# TELM0002ADC.net
KiCad netlist of a schematic drawn in Altium Designer
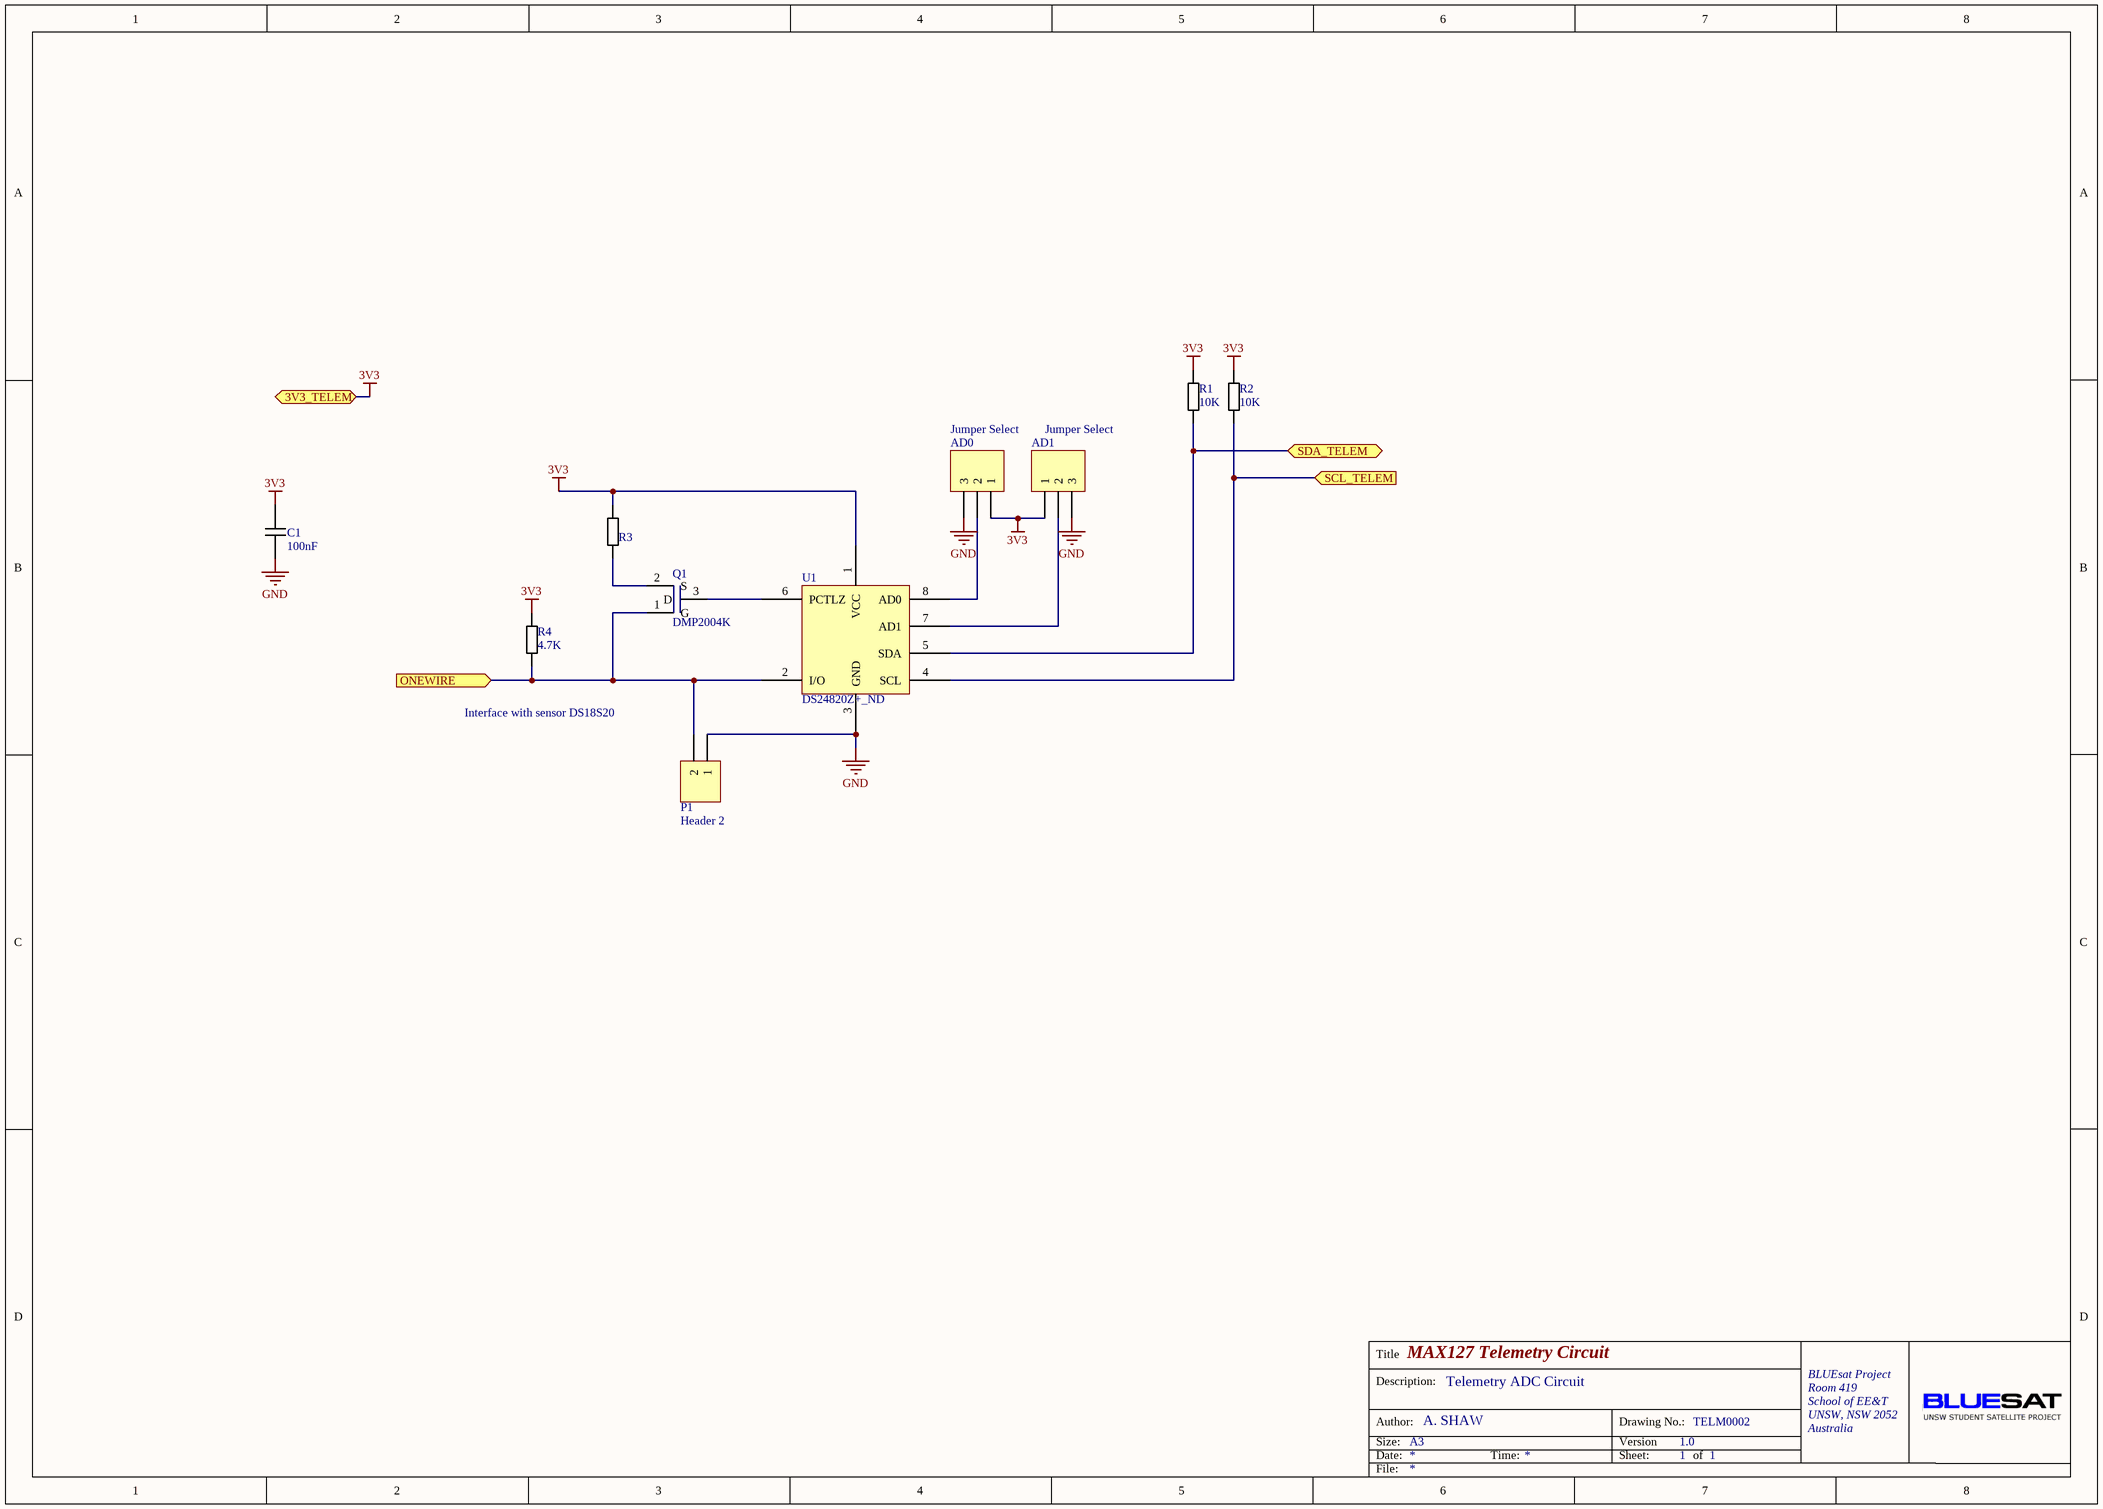
[diagram p0: TELM0002ADC.SchDoc]

(export (version "E")
  (design (tool "Eeschema 10.0.6"))
  (components
    (comp (ref "AD0")
      (value "Jumper Select")
      (footprint "SOLDER_JUMPER_3_A")
      (description "Header, 3-Pin")
      (libsource (lib "Miscellaneous Connectors") (part "Header 3"))
    )
    (comp (ref "AD1")
      (value "Jumper Select")
      (footprint "SOLDER_JUMPER_3_A")
      (description "Header, 3-Pin")
      (libsource (lib "") (part "Header 3_1"))
    )
    (comp (ref "C1")
      (value "100nF")
      (footprint "0805 Cap")
      (description "0805 MLCC - X7R, 10%")
      (fields (field (name "Comment") "0805 Cap"))
      (libsource (lib "Schlib1") (part "0805 MLCC - X7R, 10%"))
    )
    (comp (ref "P1")
      (value "Header 2")
      (footprint "HDR1X2")
      (description "Header, 2-Pin")
      (libsource (lib "Miscellaneous Connectors") (part "Header 2"))
    )
    (comp (ref "Q1")
      (value "DMP2004K")
      (footprint "DMP2004KDITR-ND")
      (description "MOSFET P-CH 20V 600MA SOT23-3")
      (libsource (lib "Telemetry") (part "DMP2004K"))
    )
    (comp (ref "R1")
      (value "10K")
      (footprint "0805 Resistor")
      (description "0805 Thick Film Resistor 1%")
      (fields (field (name "Comment") "0805 Resistor"))
      (libsource (lib "Schlib1") (part "0805 Thick Film Resistor 1%"))
    )
    (comp (ref "R2")
      (value "10K")
      (footprint "0805 Resistor")
      (description "0805 Thick Film Resistor 1%")
      (fields (field (name "Comment") "0805 Resistor"))
      (libsource (lib "Schlib1") (part "0805 Thick Film Resistor 1%"))
    )
    (comp (ref "R3")
      (value "PTC Fuse")
      (footprint "0805 Resistor")
      (description "0805 PTC Fuse")
      (fields (field (name "MANUFACTURER") "Bel Fuse Inc"))
      (libsource (lib "Tray 1 Expansion Board Prototype") (part "0805 PTC Fuse"))
    )
    (comp (ref "R4")
      (value "4.7K")
      (footprint "0805 Resistor")
      (description "0603 Thick Film Resistor 1%")
      (fields (field (name "Comment") "0603 Resistor"))
      (libsource (lib "Schlib1") (part "0603 Thick Film Resistor 1%"))
    )
    (comp (ref "U1")
      (value "DS24820Z+_ND")
      (footprint "DS2482-100")
      (description "I2C to 1-Wire Master")
      (libsource (lib "Telemetry") (part "DS24820Z+_ND"))
    )
  )
  (nets
    (net (code "1") (name "/ONEWIRE") (class "Default")
      (node (ref "P1") (pin "2") (pinfunction "2_2") (pintype "passive"))
      (node (ref "Q1") (pin "1") (pinfunction "G_1") (pintype "passive"))
      (node (ref "R4") (pin "1") (pinfunction "1_1") (pintype "passive"))
      (node (ref "U1") (pin "2") (pinfunction "I/O_2") (pintype "passive"))
    )
    (net (code "2") (name "/SCL_TELEM") (class "Default")
      (node (ref "R2") (pin "1") (pinfunction "1_1") (pintype "passive"))
      (node (ref "U1") (pin "4") (pinfunction "SCL_4") (pintype "passive"))
    )
    (net (code "3") (name "/SDA_TELEM") (class "Default")
      (node (ref "R1") (pin "1") (pinfunction "1_1") (pintype "passive"))
      (node (ref "U1") (pin "5") (pinfunction "SDA_5") (pintype "passive"))
    )
    (net (code "4") (name "3V3") (class "Default")
      (node (ref "AD0") (pin "1") (pinfunction "1_1") (pintype "passive"))
      (node (ref "AD1") (pin "1") (pinfunction "1_1") (pintype "passive"))
      (node (ref "C1") (pin "2") (pinfunction "2_2") (pintype "passive"))
      (node (ref "R1") (pin "2") (pinfunction "2_2") (pintype "passive"))
      (node (ref "R2") (pin "2") (pinfunction "2_2") (pintype "passive"))
      (node (ref "R3") (pin "2") (pinfunction "2_2") (pintype "passive"))
      (node (ref "R4") (pin "2") (pinfunction "2_2") (pintype "passive"))
      (node (ref "U1") (pin "1") (pinfunction "VCC_1") (pintype "passive"))
    )
    (net (code "5") (name "GND") (class "Default")
      (node (ref "AD0") (pin "3") (pinfunction "3_3") (pintype "passive"))
      (node (ref "AD1") (pin "3") (pinfunction "3_3") (pintype "passive"))
      (node (ref "C1") (pin "1") (pinfunction "1_1") (pintype "passive"))
      (node (ref "P1") (pin "1") (pinfunction "1_1") (pintype "passive"))
      (node (ref "U1") (pin "3") (pinfunction "GND_3") (pintype "passive"))
    )
    (net (code "6") (name "Net-(Q1-D)") (class "Default")
      (node (ref "Q1") (pin "3") (pinfunction "D_3") (pintype "passive"))
      (node (ref "U1") (pin "6") (pinfunction "PCTLZ_6") (pintype "passive"))
    )
    (net (code "7") (name "Net-(Q1-S)") (class "Default")
      (node (ref "Q1") (pin "2") (pinfunction "S_2") (pintype "passive"))
      (node (ref "R3") (pin "1") (pinfunction "1_1") (pintype "passive"))
    )
    (net (code "8") (name "Net-(U1-AD0)") (class "Default")
      (node (ref "AD0") (pin "2") (pinfunction "2_2") (pintype "passive"))
      (node (ref "U1") (pin "8") (pinfunction "AD0_8") (pintype "passive"))
    )
    (net (code "9") (name "Net-(U1-AD1)") (class "Default")
      (node (ref "AD1") (pin "2") (pinfunction "2_2") (pintype "passive"))
      (node (ref "U1") (pin "7") (pinfunction "AD1_7") (pintype "passive"))
    )
  )
)
